# RS-485.net
KiCad netlist of a schematic drawn in Altium Designer
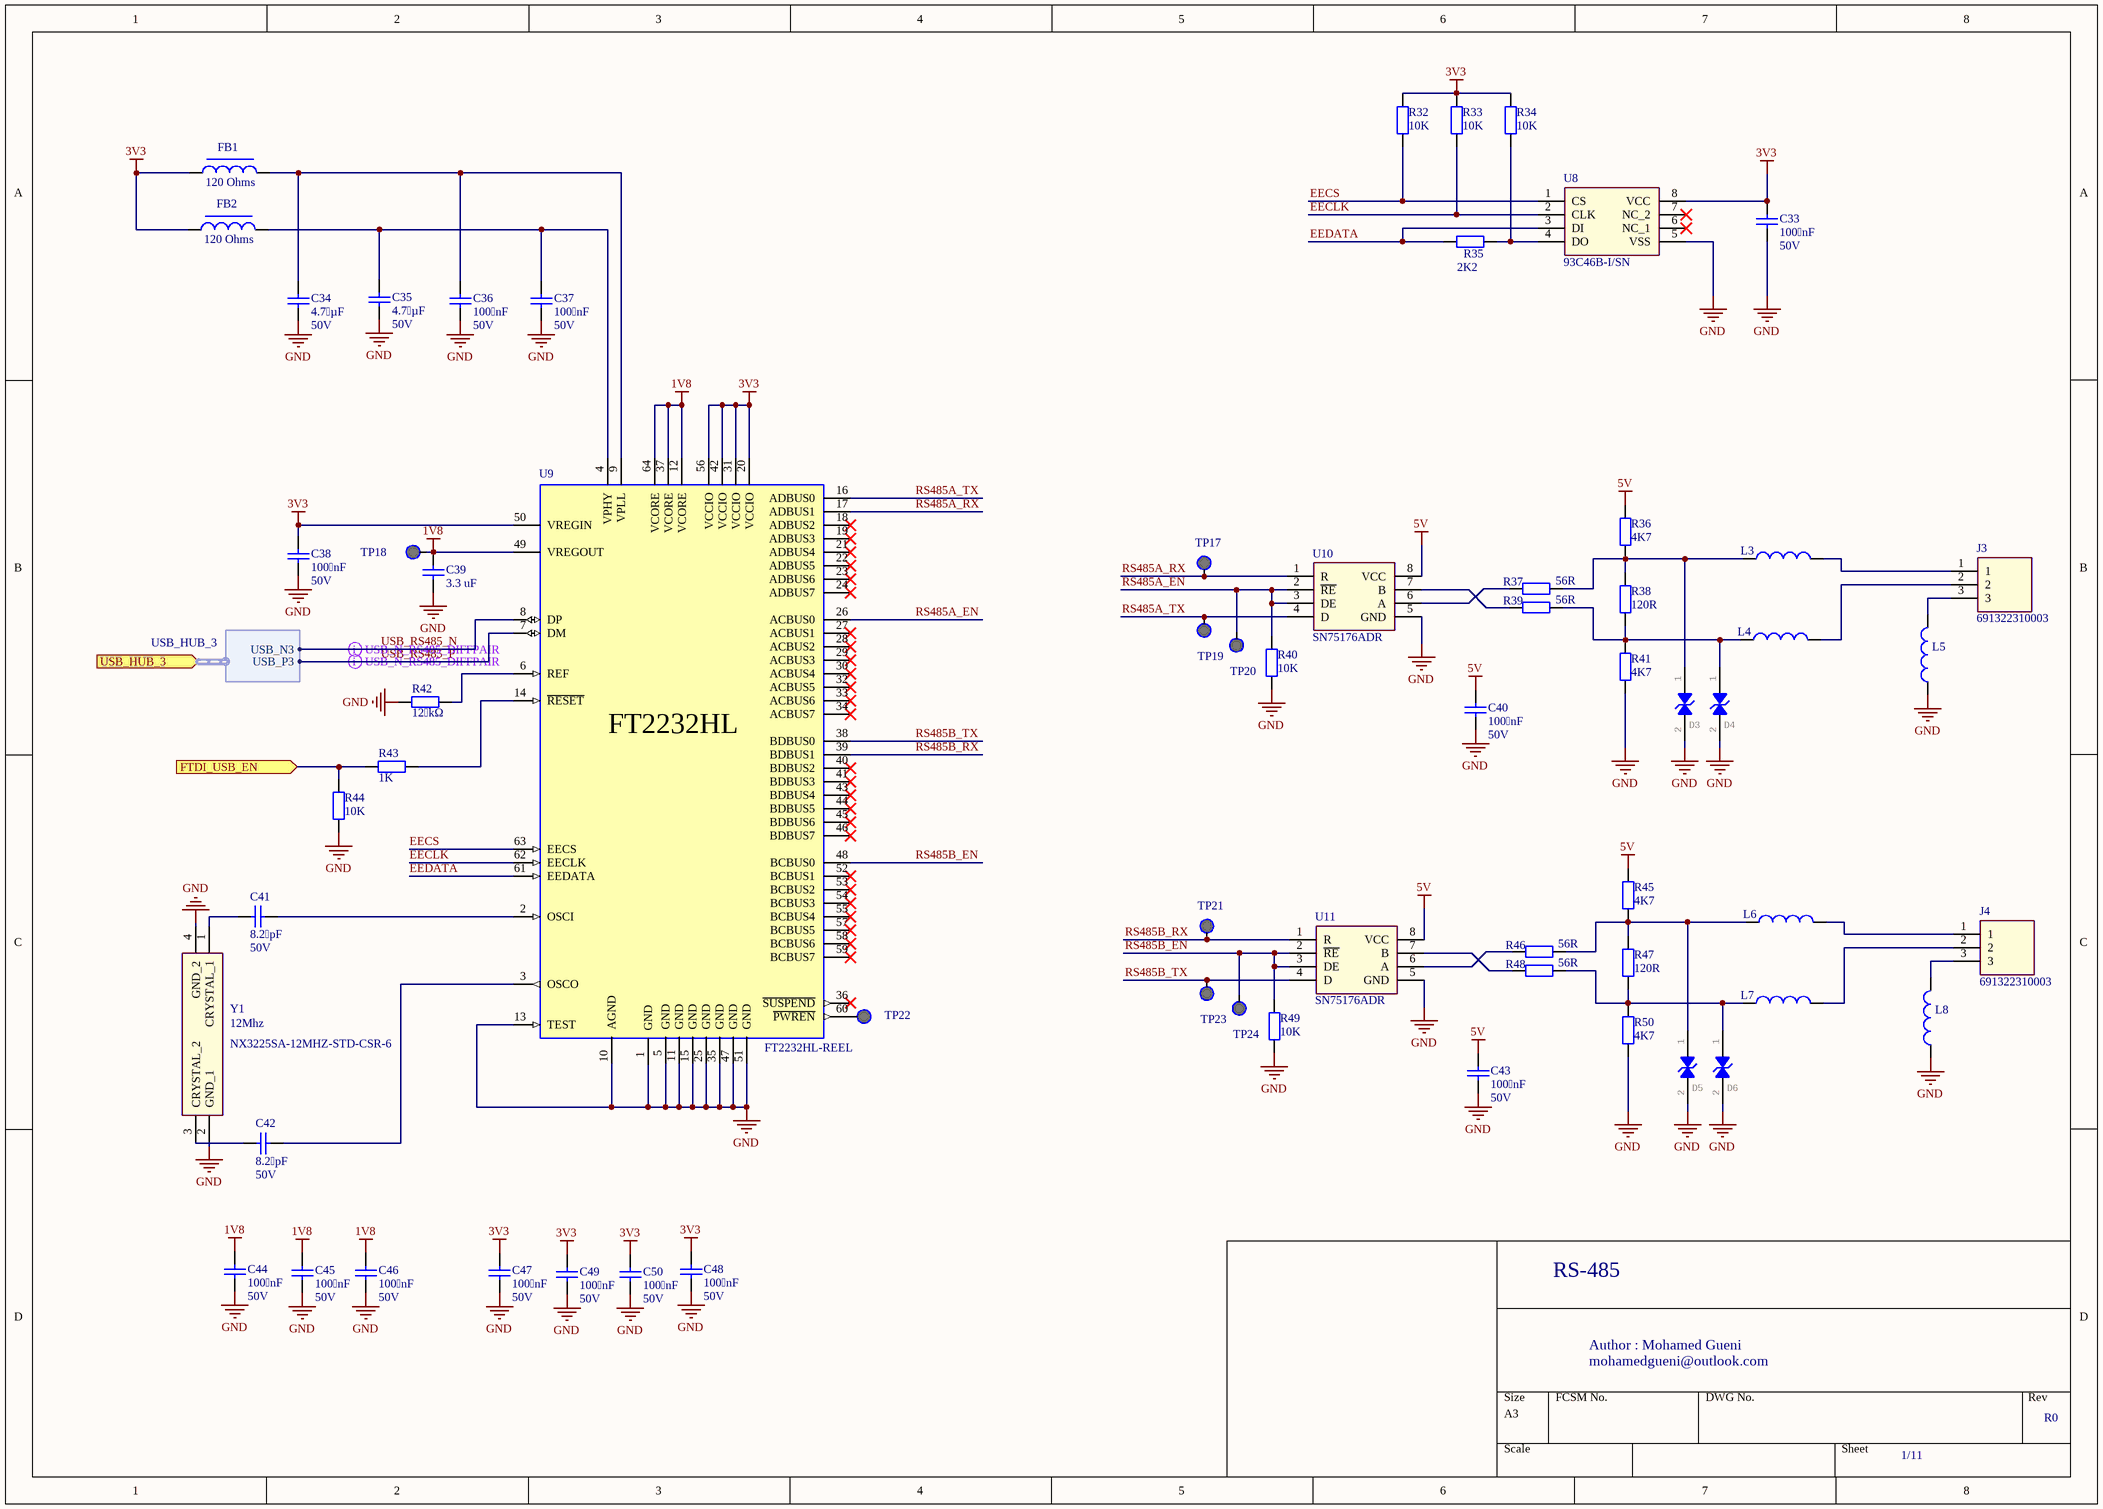
[diagram p0: RS-485.SchDoc]

(export (version "E")
  (design (tool "Eeschema 10.0.6"))
  (components
    (comp (ref "C33")
      (value "GRM188R71H104KA93D")
      (footprint "CAPC1608N")
      (fields
        (field (name "PART NUMBER") "CAP-000000017")
        (field (name "VALUE 1") "100 nF")
        (field (name "VALUE 2") "50V")
      )
      (libsource (lib "DB") (part "Capacitor"))
    )
    (comp (ref "C34")
      (value "GRM188R61H475KE11D")
      (footprint "CAPC1608N")
      (fields
        (field (name "PART NUMBER") "CAP-000000021")
        (field (name "VALUE 1") "4.7 µF")
        (field (name "VALUE 2") "50V")
      )
      (libsource (lib "DB") (part "Capacitor"))
    )
    (comp (ref "C35")
      (value "GRM188R61H475KE11D")
      (footprint "CAPC1608N")
      (fields
        (field (name "PART NUMBER") "CAP-000000021")
        (field (name "VALUE 1") "4.7 µF")
        (field (name "VALUE 2") "50V")
      )
      (libsource (lib "DB") (part "Capacitor"))
    )
    (comp (ref "C36")
      (value "GRM188R71H104KA93D")
      (footprint "CAPC1608N")
      (fields
        (field (name "PART NUMBER") "CAP-000000017")
        (field (name "VALUE 1") "100 nF")
        (field (name "VALUE 2") "50V")
      )
      (libsource (lib "DB") (part "Capacitor"))
    )
    (comp (ref "C37")
      (value "GRM188R71H104KA93D")
      (footprint "CAPC1608N")
      (fields
        (field (name "PART NUMBER") "CAP-000000017")
        (field (name "VALUE 1") "100 nF")
        (field (name "VALUE 2") "50V")
      )
      (libsource (lib "DB") (part "Capacitor"))
    )
    (comp (ref "C38")
      (value "GRM188R71H104KA93D")
      (footprint "CAPC1608N")
      (fields
        (field (name "PART NUMBER") "CAP-000000017")
        (field (name "VALUE 1") "100 nF")
        (field (name "VALUE 2") "50V")
      )
      (libsource (lib "DB") (part "Capacitor"))
    )
    (comp (ref "C39")
      (value "~")
      (footprint "CAPC1608N")
      (fields (field (name "PART NUMBER") "CAP-000000008") (field (name "VALUE 1") "3.3 uF"))
      (libsource (lib "DB") (part "Capacitor"))
    )
    (comp (ref "C40")
      (value "GRM188R71H104KA93D")
      (footprint "CAPC1608N")
      (fields
        (field (name "PART NUMBER") "CAP-000000017")
        (field (name "VALUE 1") "100 nF")
        (field (name "VALUE 2") "50V")
      )
      (libsource (lib "DB") (part "Capacitor"))
    )
    (comp (ref "C41")
      (value "GRM1555C1H8R2CA01D")
      (footprint "CAPC402")
      (fields
        (field (name "PART NUMBER") "CAP-000000013")
        (field (name "VALUE 1") "8.2 pF")
        (field (name "VALUE 2") "50V")
      )
      (libsource (lib "DB") (part "Capacitor"))
    )
    (comp (ref "C42")
      (value "GRM1555C1H8R2CA01D")
      (footprint "CAPC402")
      (fields
        (field (name "PART NUMBER") "CAP-000000013")
        (field (name "VALUE 1") "8.2 pF")
        (field (name "VALUE 2") "50V")
      )
      (libsource (lib "DB") (part "Capacitor"))
    )
    (comp (ref "C43")
      (value "GRM188R71H104KA93D")
      (footprint "CAPC1608N")
      (fields
        (field (name "PART NUMBER") "CAP-000000017")
        (field (name "VALUE 1") "100 nF")
        (field (name "VALUE 2") "50V")
      )
      (libsource (lib "DB") (part "Capacitor"))
    )
    (comp (ref "C44")
      (value "GRM188R71H104KA93D")
      (footprint "CAPC1608N")
      (fields
        (field (name "PART NUMBER") "CAP-000000017")
        (field (name "VALUE 1") "100 nF")
        (field (name "VALUE 2") "50V")
      )
      (libsource (lib "DB") (part "Capacitor"))
    )
    (comp (ref "C45")
      (value "GRM188R71H104KA93D")
      (footprint "CAPC1608N")
      (fields
        (field (name "PART NUMBER") "CAP-000000017")
        (field (name "VALUE 1") "100 nF")
        (field (name "VALUE 2") "50V")
      )
      (libsource (lib "DB") (part "Capacitor"))
    )
    (comp (ref "C46")
      (value "GRM188R71H104KA93D")
      (footprint "CAPC1608N")
      (fields
        (field (name "PART NUMBER") "CAP-000000017")
        (field (name "VALUE 1") "100 nF")
        (field (name "VALUE 2") "50V")
      )
      (libsource (lib "DB") (part "Capacitor"))
    )
    (comp (ref "C47")
      (value "GRM188R71H104KA93D")
      (footprint "CAPC1608N")
      (fields
        (field (name "PART NUMBER") "CAP-000000017")
        (field (name "VALUE 1") "100 nF")
        (field (name "VALUE 2") "50V")
      )
      (libsource (lib "DB") (part "Capacitor"))
    )
    (comp (ref "C48")
      (value "GRM188R71H104KA93D")
      (footprint "CAPC1608N")
      (fields
        (field (name "PART NUMBER") "CAP-000000017")
        (field (name "VALUE 1") "100 nF")
        (field (name "VALUE 2") "50V")
      )
      (libsource (lib "DB") (part "Capacitor"))
    )
    (comp (ref "C49")
      (value "GRM188R71H104KA93D")
      (footprint "CAPC1608N")
      (fields
        (field (name "PART NUMBER") "CAP-000000017")
        (field (name "VALUE 1") "100 nF")
        (field (name "VALUE 2") "50V")
      )
      (libsource (lib "DB") (part "Capacitor"))
    )
    (comp (ref "C50")
      (value "GRM188R71H104KA93D")
      (footprint "CAPC1608N")
      (fields
        (field (name "PART NUMBER") "CAP-000000017")
        (field (name "VALUE 1") "100 nF")
        (field (name "VALUE 2") "50V")
      )
      (libsource (lib "DB") (part "Capacitor"))
    )
    (comp (ref "D3")
      (value "CDSOD323-T12LC")
      (footprint "CDSOD323T12LC")
      (fields (field (name "PART NUMBER") "TVS-000000003"))
      (libsource (lib "DB") (part "TVSBI"))
    )
    (comp (ref "D4")
      (value "CDSOD323-T12LC")
      (footprint "CDSOD323T12LC")
      (fields (field (name "PART NUMBER") "TVS-000000003"))
      (libsource (lib "DB") (part "TVSBI"))
    )
    (comp (ref "D5")
      (value "CDSOD323-T12LC")
      (footprint "CDSOD323T12LC")
      (fields (field (name "PART NUMBER") "TVS-000000003"))
      (libsource (lib "DB") (part "TVSBI"))
    )
    (comp (ref "D6")
      (value "CDSOD323-T12LC")
      (footprint "CDSOD323T12LC")
      (fields (field (name "PART NUMBER") "TVS-000000003"))
      (libsource (lib "DB") (part "TVSBI"))
    )
    (comp (ref "FB1")
      (value "BLM18PG121SN1D")
      (footprint "BLM18SP221SN1B")
      (fields (field (name "PART NUMBER") "F-000000001") (field (name "VALUE 1") "120 Ohms"))
      (libsource (lib "DB") (part "FERRIT"))
    )
    (comp (ref "FB2")
      (value "BLM18PG121SN1D")
      (footprint "BLM18SP221SN1B")
      (fields (field (name "PART NUMBER") "F-000000001") (field (name "VALUE 1") "120 Ohms"))
      (libsource (lib "DB") (part "FERRIT"))
    )
    (comp (ref "J3")
      (value "691322310003")
      (footprint "691322310003")
      (fields (field (name "PART NUMBER") "CON-000000011"))
      (libsource (lib "DB") (part "691322310003"))
    )
    (comp (ref "J4")
      (value "691322310003")
      (footprint "691322310003")
      (fields (field (name "PART NUMBER") "CON-000000011"))
      (libsource (lib "DB") (part "691322310003"))
    )
    (comp (ref "L3")
      (value "MAF0603FAL330BT000")
      (footprint "BEADC0603X33N")
      (fields (field (name "PART NUMBER") "IND-000000006"))
      (libsource (lib "DB") (part "Inductor"))
    )
    (comp (ref "L4")
      (value "MAF0603FAL330BT000")
      (footprint "BEADC0603X33N")
      (fields (field (name "PART NUMBER") "IND-000000006"))
      (libsource (lib "DB") (part "Inductor"))
    )
    (comp (ref "L5")
      (value "MAF0603FAL330BT000")
      (footprint "BEADC0603X33N")
      (fields (field (name "PART NUMBER") "IND-000000006"))
      (libsource (lib "DB") (part "Inductor"))
    )
    (comp (ref "L6")
      (value "MAF0603FAL330BT000")
      (footprint "BEADC0603X33N")
      (fields (field (name "PART NUMBER") "IND-000000006"))
      (libsource (lib "DB") (part "Inductor"))
    )
    (comp (ref "L7")
      (value "MAF0603FAL330BT000")
      (footprint "BEADC0603X33N")
      (fields (field (name "PART NUMBER") "IND-000000006"))
      (libsource (lib "DB") (part "Inductor"))
    )
    (comp (ref "L8")
      (value "MAF0603FAL330BT000")
      (footprint "BEADC0603X33N")
      (fields (field (name "PART NUMBER") "IND-000000006"))
      (libsource (lib "DB") (part "Inductor"))
    )
    (comp (ref "R32")
      (value "RN731JTTD1002F25")
      (footprint "RESC1608N")
      (fields (field (name "PART NUMBER") "RES-000000007") (field (name "VALUE 1") "10K"))
      (libsource (lib "DB") (part "Resistor"))
    )
    (comp (ref "R33")
      (value "RN731JTTD1002F25")
      (footprint "RESC1608N")
      (fields (field (name "PART NUMBER") "RES-000000007") (field (name "VALUE 1") "10K"))
      (libsource (lib "DB") (part "Resistor"))
    )
    (comp (ref "R34")
      (value "RN731JTTD1002F25")
      (footprint "RESC1608N")
      (fields (field (name "PART NUMBER") "RES-000000007") (field (name "VALUE 1") "10K"))
      (libsource (lib "DB") (part "Resistor"))
    )
    (comp (ref "R35")
      (value "RN731JTTD2201F25")
      (footprint "RESC1608N")
      (fields (field (name "PART NUMBER") "RES-000000006") (field (name "VALUE 1") "2K2"))
      (libsource (lib "") (part "Resistor_1"))
    )
    (comp (ref "R36")
      (value "~")
      (footprint "RESC1608N")
      (fields (field (name "PART NUMBER") "RES-000000010") (field (name "VALUE 1") "4K7"))
      (libsource (lib "DB") (part "Resistor"))
    )
    (comp (ref "R37")
      (value "~")
      (footprint "RESC1608N")
      (fields (field (name "PART NUMBER") "RES-000000012") (field (name "VALUE 1") "56R"))
      (libsource (lib "") (part "Resistor_1"))
    )
    (comp (ref "R38")
      (value "~")
      (footprint "RESC1608N")
      (fields (field (name "PART NUMBER") "RES-000000013") (field (name "VALUE 1") "120R"))
      (libsource (lib "DB") (part "Resistor"))
    )
    (comp (ref "R39")
      (value "~")
      (footprint "RESC1608N")
      (fields (field (name "PART NUMBER") "RES-000000012") (field (name "VALUE 1") "56R"))
      (libsource (lib "") (part "Resistor_1"))
    )
    (comp (ref "R40")
      (value "RN731JTTD1002F25")
      (footprint "RESC1608N")
      (fields (field (name "PART NUMBER") "RES-000000007") (field (name "VALUE 1") "10K"))
      (libsource (lib "DB") (part "Resistor"))
    )
    (comp (ref "R41")
      (value "~")
      (footprint "RESC1608N")
      (fields (field (name "PART NUMBER") "RES-000000010") (field (name "VALUE 1") "4K7"))
      (libsource (lib "DB") (part "Resistor"))
    )
    (comp (ref "R42")
      (value "ERJ-3EKF1202V")
      (footprint "RESC1608N")
      (fields (field (name "PART NUMBER") "RES-0000000011") (field (name "VALUE 1") "12 kΩ"))
      (libsource (lib "") (part "Resistor_1"))
    )
    (comp (ref "R43")
      (value "RN731JTTD1001F25")
      (footprint "RESC1608N")
      (fields (field (name "PART NUMBER") "RES-000000001") (field (name "VALUE 1") "1K"))
      (libsource (lib "") (part "Resistor_1"))
    )
    (comp (ref "R44")
      (value "RN731JTTD1002F25")
      (footprint "RESC1608N")
      (fields (field (name "PART NUMBER") "RES-000000007") (field (name "VALUE 1") "10K"))
      (libsource (lib "DB") (part "Resistor"))
    )
    (comp (ref "R45")
      (value "~")
      (footprint "RESC1608N")
      (fields (field (name "PART NUMBER") "RES-000000010") (field (name "VALUE 1") "4K7"))
      (libsource (lib "DB") (part "Resistor"))
    )
    (comp (ref "R46")
      (value "~")
      (footprint "RESC1608N")
      (fields (field (name "PART NUMBER") "RES-000000012") (field (name "VALUE 1") "56R"))
      (libsource (lib "") (part "Resistor_1"))
    )
    (comp (ref "R47")
      (value "~")
      (footprint "RESC1608N")
      (fields (field (name "PART NUMBER") "RES-000000013") (field (name "VALUE 1") "120R"))
      (libsource (lib "DB") (part "Resistor"))
    )
    (comp (ref "R48")
      (value "~")
      (footprint "RESC1608N")
      (fields (field (name "PART NUMBER") "RES-000000012") (field (name "VALUE 1") "56R"))
      (libsource (lib "") (part "Resistor_1"))
    )
    (comp (ref "R49")
      (value "RN731JTTD1002F25")
      (footprint "RESC1608N")
      (fields (field (name "PART NUMBER") "RES-000000007") (field (name "VALUE 1") "10K"))
      (libsource (lib "DB") (part "Resistor"))
    )
    (comp (ref "R50")
      (value "~")
      (footprint "RESC1608N")
      (fields (field (name "PART NUMBER") "RES-000000010") (field (name "VALUE 1") "4K7"))
      (libsource (lib "DB") (part "Resistor"))
    )
    (comp (ref "TP17")
      (value "Test Point")
      (footprint "TP")
      (fields (field (name "PART NUMBER") "MIS-000000002"))
      (libsource (lib "DB") (part "TP"))
    )
    (comp (ref "TP18")
      (value "Test Point")
      (footprint "TP")
      (fields (field (name "PART NUMBER") "MIS-000000002"))
      (libsource (lib "DB") (part "TP"))
    )
    (comp (ref "TP19")
      (value "Test Point")
      (footprint "TP")
      (fields (field (name "PART NUMBER") "MIS-000000002"))
      (libsource (lib "DB") (part "TP"))
    )
    (comp (ref "TP20")
      (value "Test Point")
      (footprint "TP")
      (fields (field (name "PART NUMBER") "MIS-000000002"))
      (libsource (lib "DB") (part "TP"))
    )
    (comp (ref "TP21")
      (value "Test Point")
      (footprint "TP")
      (fields (field (name "PART NUMBER") "MIS-000000002"))
      (libsource (lib "DB") (part "TP"))
    )
    (comp (ref "TP22")
      (value "Test Point")
      (footprint "TP")
      (fields (field (name "PART NUMBER") "MIS-000000002"))
      (libsource (lib "DB") (part "TP"))
    )
    (comp (ref "TP23")
      (value "Test Point")
      (footprint "TP")
      (fields (field (name "PART NUMBER") "MIS-000000002"))
      (libsource (lib "DB") (part "TP"))
    )
    (comp (ref "TP24")
      (value "Test Point")
      (footprint "TP")
      (fields (field (name "PART NUMBER") "MIS-000000002"))
      (libsource (lib "DB") (part "TP"))
    )
    (comp (ref "U8")
      (value "93C46B-I/SN")
      (footprint "SOIC127P600X175-8N")
      (fields (field (name "PART NUMBER") "GIC-000000012"))
      (libsource (lib "DB") (part "93C46B-I/SN"))
    )
    (comp (ref "U9")
      (value "FT2232HL-REEL")
      (footprint "LQFP-64")
      (fields (field (name "PART NUMBER") "GIC-000000005"))
      (libsource (lib "DB") (part "FT2232H"))
    )
    (comp (ref "U10")
      (value "SN75176ADR")
      (footprint "SOIC127P600X175-8N")
      (fields (field (name "PART NUMBER") "GIC-000000013"))
      (libsource (lib "DB") (part "SN75176ADR"))
    )
    (comp (ref "U11")
      (value "SN75176ADR")
      (footprint "SOIC127P600X175-8N")
      (fields (field (name "PART NUMBER") "GIC-000000013"))
      (libsource (lib "DB") (part "SN75176ADR"))
    )
    (comp (ref "Y1")
      (value "NX3225SA-12MHZ-STD-CSR-6")
      (footprint "NX3225SA")
      (fields (field (name "PART NUMBER") "Y-000000002") (field (name "VALUE 1") "12Mhz"))
      (libsource (lib "DB") (part "NX3225SA"))
    )
  )
  (nets
    (net (code "2") (name "/EECLK") (class "Default")
      (node (ref "R33") (pin "1") (pinfunction "1_1") (pintype "passive"))
      (node (ref "U8") (pin "2") (pinfunction "CLK_2") (pintype "passive"))
      (node (ref "U9") (pin "62") (pinfunction "EECLK_62") (pintype "input"))
    )
    (net (code "3") (name "/EECS") (class "Default")
      (node (ref "R32") (pin "1") (pinfunction "1_1") (pintype "passive"))
      (node (ref "U8") (pin "1") (pinfunction "CS_1") (pintype "passive"))
      (node (ref "U9") (pin "63") (pinfunction "EECS_63") (pintype "input"))
    )
    (net (code "4") (name "/EEDATA") (class "Default")
      (node (ref "R35") (pin "1") (pinfunction "1_1") (pintype "passive"))
      (node (ref "U8") (pin "3") (pinfunction "DI_3") (pintype "passive"))
      (node (ref "U9") (pin "61") (pinfunction "EEDATA_61") (pintype "input"))
    )
    (net (code "5") (name "/FTDI_USB_EN") (class "Default")
      (node (ref "R43") (pin "1") (pinfunction "1_1") (pintype "passive"))
      (node (ref "R44") (pin "2") (pinfunction "2_2") (pintype "passive"))
    )
    (net (code "6") (name "/RS485A_EN") (class "Default")
      (node (ref "R40") (pin "2") (pinfunction "2_2") (pintype "passive"))
      (node (ref "TP20") (pin "1") (pinfunction "1_1") (pintype "passive"))
      (node (ref "U10") (pin "2") (pinfunction "RE_2") (pintype "passive"))
      (node (ref "U10") (pin "3") (pinfunction "DE_3") (pintype "passive"))
      (node (ref "U9") (pin "26") (pinfunction "ACBUS0_26") (pintype "passive"))
    )
    (net (code "7") (name "/RS485A_RX") (class "Default")
      (node (ref "TP17") (pin "1") (pinfunction "1_1") (pintype "passive"))
      (node (ref "U10") (pin "1") (pinfunction "R_1") (pintype "passive"))
      (node (ref "U9") (pin "17") (pinfunction "ADBUS1_17") (pintype "passive"))
    )
    (net (code "8") (name "/RS485A_TX") (class "Default")
      (node (ref "TP19") (pin "1") (pinfunction "1_1") (pintype "passive"))
      (node (ref "U10") (pin "4") (pinfunction "D_4") (pintype "passive"))
      (node (ref "U9") (pin "16") (pinfunction "ADBUS0_16") (pintype "passive"))
    )
    (net (code "9") (name "/RS485B_EN") (class "Default")
      (node (ref "R49") (pin "2") (pinfunction "2_2") (pintype "passive"))
      (node (ref "TP24") (pin "1") (pinfunction "1_1") (pintype "passive"))
      (node (ref "U11") (pin "2") (pinfunction "RE_2") (pintype "passive"))
      (node (ref "U11") (pin "3") (pinfunction "DE_3") (pintype "passive"))
      (node (ref "U9") (pin "48") (pinfunction "BCBUS0_48") (pintype "passive"))
    )
    (net (code "10") (name "/RS485B_RX") (class "Default")
      (node (ref "TP21") (pin "1") (pinfunction "1_1") (pintype "passive"))
      (node (ref "U11") (pin "1") (pinfunction "R_1") (pintype "passive"))
      (node (ref "U9") (pin "39") (pinfunction "BDBUS1_39") (pintype "passive"))
    )
    (net (code "11") (name "/RS485B_TX") (class "Default")
      (node (ref "TP23") (pin "1") (pinfunction "1_1") (pintype "passive"))
      (node (ref "U11") (pin "4") (pinfunction "D_4") (pintype "passive"))
      (node (ref "U9") (pin "38") (pinfunction "BDBUS0_38") (pintype "passive"))
    )
    (net (code "12") (name "/USB_RS485_N") (class "Default")
      (node (ref "U9") (pin "8") (pinfunction "DP_8") (pintype "bidirectional"))
    )
    (net (code "13") (name "/USB_RS485_P") (class "Default")
      (node (ref "U9") (pin "7") (pinfunction "DM_7") (pintype "bidirectional"))
    )
    (net (code "15") (name "1V8") (class "Default")
      (node (ref "C39") (pin "2") (pinfunction "2_2") (pintype "passive"))
      (node (ref "C44") (pin "2") (pinfunction "2_2") (pintype "passive"))
      (node (ref "C45") (pin "2") (pinfunction "2_2") (pintype "passive"))
      (node (ref "C46") (pin "2") (pinfunction "2_2") (pintype "passive"))
      (node (ref "TP18") (pin "1") (pinfunction "1_1") (pintype "passive"))
      (node (ref "U9") (pin "12") (pinfunction "VCORE_12") (pintype "power_in"))
      (node (ref "U9") (pin "37") (pinfunction "VCORE_37") (pintype "power_in"))
      (node (ref "U9") (pin "49") (pinfunction "VREGOUT_49") (pintype "power_in"))
      (node (ref "U9") (pin "64") (pinfunction "VCORE_64") (pintype "power_in"))
    )
    (net (code "16") (name "3V3") (class "Default")
      (node (ref "C33") (pin "2") (pinfunction "2_2") (pintype "passive"))
      (node (ref "C38") (pin "2") (pinfunction "2_2") (pintype "passive"))
      (node (ref "C47") (pin "2") (pinfunction "2_2") (pintype "passive"))
      (node (ref "C48") (pin "2") (pinfunction "2_2") (pintype "passive"))
      (node (ref "C49") (pin "2") (pinfunction "2_2") (pintype "passive"))
      (node (ref "C50") (pin "2") (pinfunction "2_2") (pintype "passive"))
      (node (ref "FB1") (pin "1") (pinfunction "1_1") (pintype "passive"))
      (node (ref "FB2") (pin "1") (pinfunction "1_1") (pintype "passive"))
      (node (ref "R32") (pin "2") (pinfunction "2_2") (pintype "passive"))
      (node (ref "R33") (pin "2") (pinfunction "2_2") (pintype "passive"))
      (node (ref "R34") (pin "2") (pinfunction "2_2") (pintype "passive"))
      (node (ref "U8") (pin "8") (pinfunction "VCC_8") (pintype "passive"))
      (node (ref "U9") (pin "20") (pinfunction "VCCIO_20") (pintype "power_in"))
      (node (ref "U9") (pin "31") (pinfunction "VCCIO_31") (pintype "power_in"))
      (node (ref "U9") (pin "42") (pinfunction "VCCIO_42") (pintype "power_in"))
      (node (ref "U9") (pin "50") (pinfunction "VREGIN_50") (pintype "power_in"))
      (node (ref "U9") (pin "56") (pinfunction "VCCIO_56") (pintype "power_in"))
    )
    (net (code "17") (name "5V") (class "Default")
      (node (ref "C40") (pin "2") (pinfunction "2_2") (pintype "passive"))
      (node (ref "C43") (pin "2") (pinfunction "2_2") (pintype "passive"))
      (node (ref "R36") (pin "2") (pinfunction "2_2") (pintype "passive"))
      (node (ref "R45") (pin "2") (pinfunction "2_2") (pintype "passive"))
      (node (ref "U10") (pin "8") (pinfunction "VCC_8") (pintype "passive"))
      (node (ref "U11") (pin "8") (pinfunction "VCC_8") (pintype "passive"))
    )
    (net (code "18") (name "GND") (class "Default")
      (node (ref "C33") (pin "1") (pinfunction "1_1") (pintype "passive"))
      (node (ref "C34") (pin "1") (pinfunction "1_1") (pintype "passive"))
      (node (ref "C35") (pin "1") (pinfunction "1_1") (pintype "passive"))
      (node (ref "C36") (pin "1") (pinfunction "1_1") (pintype "passive"))
      (node (ref "C37") (pin "1") (pinfunction "1_1") (pintype "passive"))
      (node (ref "C38") (pin "1") (pinfunction "1_1") (pintype "passive"))
      (node (ref "C39") (pin "1") (pinfunction "1_1") (pintype "passive"))
      (node (ref "C40") (pin "1") (pinfunction "1_1") (pintype "passive"))
      (node (ref "C43") (pin "1") (pinfunction "1_1") (pintype "passive"))
      (node (ref "C44") (pin "1") (pinfunction "1_1") (pintype "passive"))
      (node (ref "C45") (pin "1") (pinfunction "1_1") (pintype "passive"))
      (node (ref "C46") (pin "1") (pinfunction "1_1") (pintype "passive"))
      (node (ref "C47") (pin "1") (pinfunction "1_1") (pintype "passive"))
      (node (ref "C48") (pin "1") (pinfunction "1_1") (pintype "passive"))
      (node (ref "C49") (pin "1") (pinfunction "1_1") (pintype "passive"))
      (node (ref "C50") (pin "1") (pinfunction "1_1") (pintype "passive"))
      (node (ref "D3") (pin "2") (pinfunction "2_2") (pintype "passive"))
      (node (ref "D4") (pin "2") (pinfunction "2_2") (pintype "passive"))
      (node (ref "D5") (pin "2") (pinfunction "2_2") (pintype "passive"))
      (node (ref "D6") (pin "2") (pinfunction "2_2") (pintype "passive"))
      (node (ref "L5") (pin "1") (pinfunction "1_1") (pintype "passive"))
      (node (ref "L8") (pin "1") (pinfunction "1_1") (pintype "passive"))
      (node (ref "R40") (pin "1") (pinfunction "1_1") (pintype "passive"))
      (node (ref "R41") (pin "1") (pinfunction "1_1") (pintype "passive"))
      (node (ref "R42") (pin "1") (pinfunction "1_1") (pintype "passive"))
      (node (ref "R44") (pin "1") (pinfunction "1_1") (pintype "passive"))
      (node (ref "R49") (pin "1") (pinfunction "1_1") (pintype "passive"))
      (node (ref "R50") (pin "1") (pinfunction "1_1") (pintype "passive"))
      (node (ref "U10") (pin "5") (pinfunction "GND_5") (pintype "passive"))
      (node (ref "U11") (pin "5") (pinfunction "GND_5") (pintype "passive"))
      (node (ref "U8") (pin "5") (pinfunction "VSS_5") (pintype "passive"))
      (node (ref "U9") (pin "1") (pinfunction "GND_1") (pintype "power_in"))
      (node (ref "U9") (pin "10") (pinfunction "AGND_10") (pintype "power_in"))
      (node (ref "U9") (pin "11") (pinfunction "GND_11") (pintype "power_in"))
      (node (ref "U9") (pin "13") (pinfunction "TEST_13") (pintype "input"))
      (node (ref "U9") (pin "15") (pinfunction "GND_15") (pintype "power_in"))
      (node (ref "U9") (pin "25") (pinfunction "GND_25") (pintype "power_in"))
      (node (ref "U9") (pin "35") (pinfunction "GND_35") (pintype "power_in"))
      (node (ref "U9") (pin "47") (pinfunction "GND_47") (pintype "power_in"))
      (node (ref "U9") (pin "5") (pinfunction "GND_5") (pintype "power_in"))
      (node (ref "U9") (pin "51") (pinfunction "GND_51") (pintype "power_in"))
      (node (ref "Y1") (pin "2") (pinfunction "GND_1_2") (pintype "passive"))
      (node (ref "Y1") (pin "4") (pinfunction "GND_2_4") (pintype "passive"))
    )
    (net (code "19") (name "Net-(D3-Pad1)") (class "Default")
      (node (ref "D3") (pin "1") (pinfunction "1_1") (pintype "passive"))
      (node (ref "L3") (pin "1") (pinfunction "1_1") (pintype "passive"))
      (node (ref "R36") (pin "1") (pinfunction "1_1") (pintype "passive"))
      (node (ref "R37") (pin "2") (pinfunction "2_2") (pintype "passive"))
      (node (ref "R38") (pin "2") (pinfunction "2_2") (pintype "passive"))
    )
    (net (code "20") (name "Net-(D4-Pad1)") (class "Default")
      (node (ref "D4") (pin "1") (pinfunction "1_1") (pintype "passive"))
      (node (ref "L4") (pin "1") (pinfunction "1_1") (pintype "passive"))
      (node (ref "R38") (pin "1") (pinfunction "1_1") (pintype "passive"))
      (node (ref "R39") (pin "2") (pinfunction "2_2") (pintype "passive"))
      (node (ref "R41") (pin "2") (pinfunction "2_2") (pintype "passive"))
    )
    (net (code "21") (name "Net-(D5-Pad1)") (class "Default")
      (node (ref "D5") (pin "1") (pinfunction "1_1") (pintype "passive"))
      (node (ref "L6") (pin "1") (pinfunction "1_1") (pintype "passive"))
      (node (ref "R45") (pin "1") (pinfunction "1_1") (pintype "passive"))
      (node (ref "R46") (pin "2") (pinfunction "2_2") (pintype "passive"))
      (node (ref "R47") (pin "2") (pinfunction "2_2") (pintype "passive"))
    )
    (net (code "22") (name "Net-(D6-Pad1)") (class "Default")
      (node (ref "D6") (pin "1") (pinfunction "1_1") (pintype "passive"))
      (node (ref "L7") (pin "1") (pinfunction "1_1") (pintype "passive"))
      (node (ref "R47") (pin "1") (pinfunction "1_1") (pintype "passive"))
      (node (ref "R48") (pin "2") (pinfunction "2_2") (pintype "passive"))
      (node (ref "R50") (pin "2") (pinfunction "2_2") (pintype "passive"))
    )
    (net (code "23") (name "Net-(J3-Pad1)") (class "Default")
      (node (ref "J3") (pin "1") (pinfunction "1_1") (pintype "passive"))
      (node (ref "L3") (pin "2") (pinfunction "2_2") (pintype "passive"))
    )
    (net (code "24") (name "Net-(J3-Pad2)") (class "Default")
      (node (ref "J3") (pin "2") (pinfunction "2_2") (pintype "passive"))
      (node (ref "L4") (pin "2") (pinfunction "2_2") (pintype "passive"))
    )
    (net (code "25") (name "Net-(J3-Pad3)") (class "Default")
      (node (ref "J3") (pin "3") (pinfunction "3_3") (pintype "passive"))
      (node (ref "L5") (pin "2") (pinfunction "2_2") (pintype "passive"))
    )
    (net (code "26") (name "Net-(J4-Pad1)") (class "Default")
      (node (ref "J4") (pin "1") (pinfunction "1_1") (pintype "passive"))
      (node (ref "L6") (pin "2") (pinfunction "2_2") (pintype "passive"))
    )
    (net (code "27") (name "Net-(J4-Pad2)") (class "Default")
      (node (ref "J4") (pin "2") (pinfunction "2_2") (pintype "passive"))
      (node (ref "L7") (pin "2") (pinfunction "2_2") (pintype "passive"))
    )
    (net (code "28") (name "Net-(J4-Pad3)") (class "Default")
      (node (ref "J4") (pin "3") (pinfunction "3_3") (pintype "passive"))
      (node (ref "L8") (pin "2") (pinfunction "2_2") (pintype "passive"))
    )
    (net (code "29") (name "Net-(U8-DO)") (class "Default")
      (node (ref "R34") (pin "1") (pinfunction "1_1") (pintype "passive"))
      (node (ref "R35") (pin "2") (pinfunction "2_2") (pintype "passive"))
      (node (ref "U8") (pin "4") (pinfunction "DO_4") (pintype "passive"))
    )
    (net (code "30") (name "Net-(U9-OSCI)") (class "Default")
      (node (ref "C41") (pin "1") (pinfunction "1_1") (pintype "passive"))
      (node (ref "U9") (pin "2") (pinfunction "OSCI_2") (pintype "input"))
    )
    (net (code "31") (name "Net-(U9-OSCO)") (class "Default")
      (node (ref "C42") (pin "1") (pinfunction "1_1") (pintype "passive"))
      (node (ref "U9") (pin "3") (pinfunction "OSCO_3") (pintype "output"))
    )
    (net (code "32") (name "Net-(U9-REF)") (class "Default")
      (node (ref "R42") (pin "2") (pinfunction "2_2") (pintype "passive"))
      (node (ref "U9") (pin "6") (pinfunction "REF_6") (pintype "input"))
    )
    (net (code "33") (name "Net-(U9-VPHY)") (class "Default")
      (node (ref "C35") (pin "2") (pinfunction "2_2") (pintype "passive"))
      (node (ref "C37") (pin "2") (pinfunction "2_2") (pintype "passive"))
      (node (ref "FB2") (pin "2") (pinfunction "2_2") (pintype "passive"))
      (node (ref "U9") (pin "4") (pinfunction "VPHY_4") (pintype "power_in"))
    )
    (net (code "34") (name "Net-(U9-VPLL)") (class "Default")
      (node (ref "C34") (pin "2") (pinfunction "2_2") (pintype "passive"))
      (node (ref "C36") (pin "2") (pinfunction "2_2") (pintype "passive"))
      (node (ref "FB1") (pin "2") (pinfunction "2_2") (pintype "passive"))
      (node (ref "U9") (pin "9") (pinfunction "VPLL_9") (pintype "power_in"))
    )
    (net (code "35") (name "Net-(U9-~{PWREN})") (class "Default")
      (node (ref "TP22") (pin "1") (pinfunction "1_1") (pintype "passive"))
      (node (ref "U9") (pin "60") (pinfunction "~{PWREN}_60") (pintype "output"))
    )
    (net (code "36") (name "Net-(U9-~{RESET})") (class "Default")
      (node (ref "R43") (pin "2") (pinfunction "2_2") (pintype "passive"))
      (node (ref "U9") (pin "14") (pinfunction "~{RESET}_14") (pintype "input"))
    )
    (net (code "37") (name "Net-(U10-A)") (class "Default")
      (node (ref "R37") (pin "1") (pinfunction "1_1") (pintype "passive"))
      (node (ref "U10") (pin "6") (pinfunction "A_6") (pintype "passive"))
    )
    (net (code "38") (name "Net-(U10-B)") (class "Default")
      (node (ref "R39") (pin "1") (pinfunction "1_1") (pintype "passive"))
      (node (ref "U10") (pin "7") (pinfunction "B_7") (pintype "passive"))
    )
    (net (code "39") (name "Net-(U11-A)") (class "Default")
      (node (ref "R46") (pin "1") (pinfunction "1_1") (pintype "passive"))
      (node (ref "U11") (pin "6") (pinfunction "A_6") (pintype "passive"))
    )
    (net (code "40") (name "Net-(U11-B)") (class "Default")
      (node (ref "R48") (pin "1") (pinfunction "1_1") (pintype "passive"))
      (node (ref "U11") (pin "7") (pinfunction "B_7") (pintype "passive"))
    )
    (net (code "41") (name "Net-(Y1-CRYSTAL_1)") (class "Default")
      (node (ref "C41") (pin "2") (pinfunction "2_2") (pintype "passive"))
      (node (ref "Y1") (pin "1") (pinfunction "CRYSTAL_1_1") (pintype "passive"))
    )
    (net (code "42") (name "Net-(Y1-CRYSTAL_2)") (class "Default")
      (node (ref "C42") (pin "2") (pinfunction "2_2") (pintype "passive"))
      (node (ref "Y1") (pin "3") (pinfunction "CRYSTAL_2_3") (pintype "passive"))
    )
    (net (code "43") (name "unconnected-(U8-NC_1-Pad6)") (class "Default")
      (node (ref "U8") (pin "6") (pinfunction "NC_1_6") (pintype "passive+no_connect"))
    )
    (net (code "44") (name "unconnected-(U8-NC_2-Pad7)") (class "Default")
      (node (ref "U8") (pin "7") (pinfunction "NC_2_7") (pintype "passive+no_connect"))
    )
    (net (code "45") (name "unconnected-(U9-ACBUS1-Pad27)") (class "Default")
      (node (ref "U9") (pin "27") (pinfunction "ACBUS1_27") (pintype "passive+no_connect"))
    )
    (net (code "46") (name "unconnected-(U9-ACBUS2-Pad28)") (class "Default")
      (node (ref "U9") (pin "28") (pinfunction "ACBUS2_28") (pintype "passive+no_connect"))
    )
    (net (code "47") (name "unconnected-(U9-ACBUS3-Pad29)") (class "Default")
      (node (ref "U9") (pin "29") (pinfunction "ACBUS3_29") (pintype "passive+no_connect"))
    )
    (net (code "48") (name "unconnected-(U9-ACBUS4-Pad30)") (class "Default")
      (node (ref "U9") (pin "30") (pinfunction "ACBUS4_30") (pintype "passive+no_connect"))
    )
    (net (code "49") (name "unconnected-(U9-ACBUS5-Pad32)") (class "Default")
      (node (ref "U9") (pin "32") (pinfunction "ACBUS5_32") (pintype "passive+no_connect"))
    )
    (net (code "50") (name "unconnected-(U9-ACBUS6-Pad33)") (class "Default")
      (node (ref "U9") (pin "33") (pinfunction "ACBUS6_33") (pintype "passive+no_connect"))
    )
    (net (code "51") (name "unconnected-(U9-ACBUS7-Pad34)") (class "Default")
      (node (ref "U9") (pin "34") (pinfunction "ACBUS7_34") (pintype "passive+no_connect"))
    )
    (net (code "52") (name "unconnected-(U9-ADBUS2-Pad18)") (class "Default")
      (node (ref "U9") (pin "18") (pinfunction "ADBUS2_18") (pintype "passive+no_connect"))
    )
    (net (code "53") (name "unconnected-(U9-ADBUS3-Pad19)") (class "Default")
      (node (ref "U9") (pin "19") (pinfunction "ADBUS3_19") (pintype "passive+no_connect"))
    )
    (net (code "54") (name "unconnected-(U9-ADBUS4-Pad21)") (class "Default")
      (node (ref "U9") (pin "21") (pinfunction "ADBUS4_21") (pintype "passive+no_connect"))
    )
    (net (code "55") (name "unconnected-(U9-ADBUS5-Pad22)") (class "Default")
      (node (ref "U9") (pin "22") (pinfunction "ADBUS5_22") (pintype "passive+no_connect"))
    )
    (net (code "56") (name "unconnected-(U9-ADBUS6-Pad23)") (class "Default")
      (node (ref "U9") (pin "23") (pinfunction "ADBUS6_23") (pintype "passive+no_connect"))
    )
    (net (code "57") (name "unconnected-(U9-ADBUS7-Pad24)") (class "Default")
      (node (ref "U9") (pin "24") (pinfunction "ADBUS7_24") (pintype "passive+no_connect"))
    )
    (net (code "58") (name "unconnected-(U9-BCBUS1-Pad52)") (class "Default")
      (node (ref "U9") (pin "52") (pinfunction "BCBUS1_52") (pintype "passive+no_connect"))
    )
    (net (code "59") (name "unconnected-(U9-BCBUS2-Pad53)") (class "Default")
      (node (ref "U9") (pin "53") (pinfunction "BCBUS2_53") (pintype "passive+no_connect"))
    )
    (net (code "60") (name "unconnected-(U9-BCBUS3-Pad54)") (class "Default")
      (node (ref "U9") (pin "54") (pinfunction "BCBUS3_54") (pintype "passive+no_connect"))
    )
    (net (code "61") (name "unconnected-(U9-BCBUS4-Pad55)") (class "Default")
      (node (ref "U9") (pin "55") (pinfunction "BCBUS4_55") (pintype "passive+no_connect"))
    )
    (net (code "62") (name "unconnected-(U9-BCBUS5-Pad57)") (class "Default")
      (node (ref "U9") (pin "57") (pinfunction "BCBUS5_57") (pintype "passive+no_connect"))
    )
    (net (code "63") (name "unconnected-(U9-BCBUS6-Pad58)") (class "Default")
      (node (ref "U9") (pin "58") (pinfunction "BCBUS6_58") (pintype "passive+no_connect"))
    )
    (net (code "64") (name "unconnected-(U9-BCBUS7-Pad59)") (class "Default")
      (node (ref "U9") (pin "59") (pinfunction "BCBUS7_59") (pintype "passive+no_connect"))
    )
    (net (code "65") (name "unconnected-(U9-BDBUS2-Pad40)") (class "Default")
      (node (ref "U9") (pin "40") (pinfunction "BDBUS2_40") (pintype "passive+no_connect"))
    )
    (net (code "66") (name "unconnected-(U9-BDBUS3-Pad41)") (class "Default")
      (node (ref "U9") (pin "41") (pinfunction "BDBUS3_41") (pintype "passive+no_connect"))
    )
    (net (code "67") (name "unconnected-(U9-BDBUS4-Pad43)") (class "Default")
      (node (ref "U9") (pin "43") (pinfunction "BDBUS4_43") (pintype "passive+no_connect"))
    )
    (net (code "68") (name "unconnected-(U9-BDBUS5-Pad44)") (class "Default")
      (node (ref "U9") (pin "44") (pinfunction "BDBUS5_44") (pintype "passive+no_connect"))
    )
    (net (code "69") (name "unconnected-(U9-BDBUS6-Pad45)") (class "Default")
      (node (ref "U9") (pin "45") (pinfunction "BDBUS6_45") (pintype "passive+no_connect"))
    )
    (net (code "70") (name "unconnected-(U9-BDBUS7-Pad46)") (class "Default")
      (node (ref "U9") (pin "46") (pinfunction "BDBUS7_46") (pintype "passive+no_connect"))
    )
    (net (code "71") (name "unconnected-(U9-~{SUSPEND}-Pad36)") (class "Default")
      (node (ref "U9") (pin "36") (pinfunction "~{SUSPEND}_36") (pintype "output+no_connect"))
    )
  )
)
